# Main_Board1.net
KiCad netlist of a schematic drawn in Altium Designer
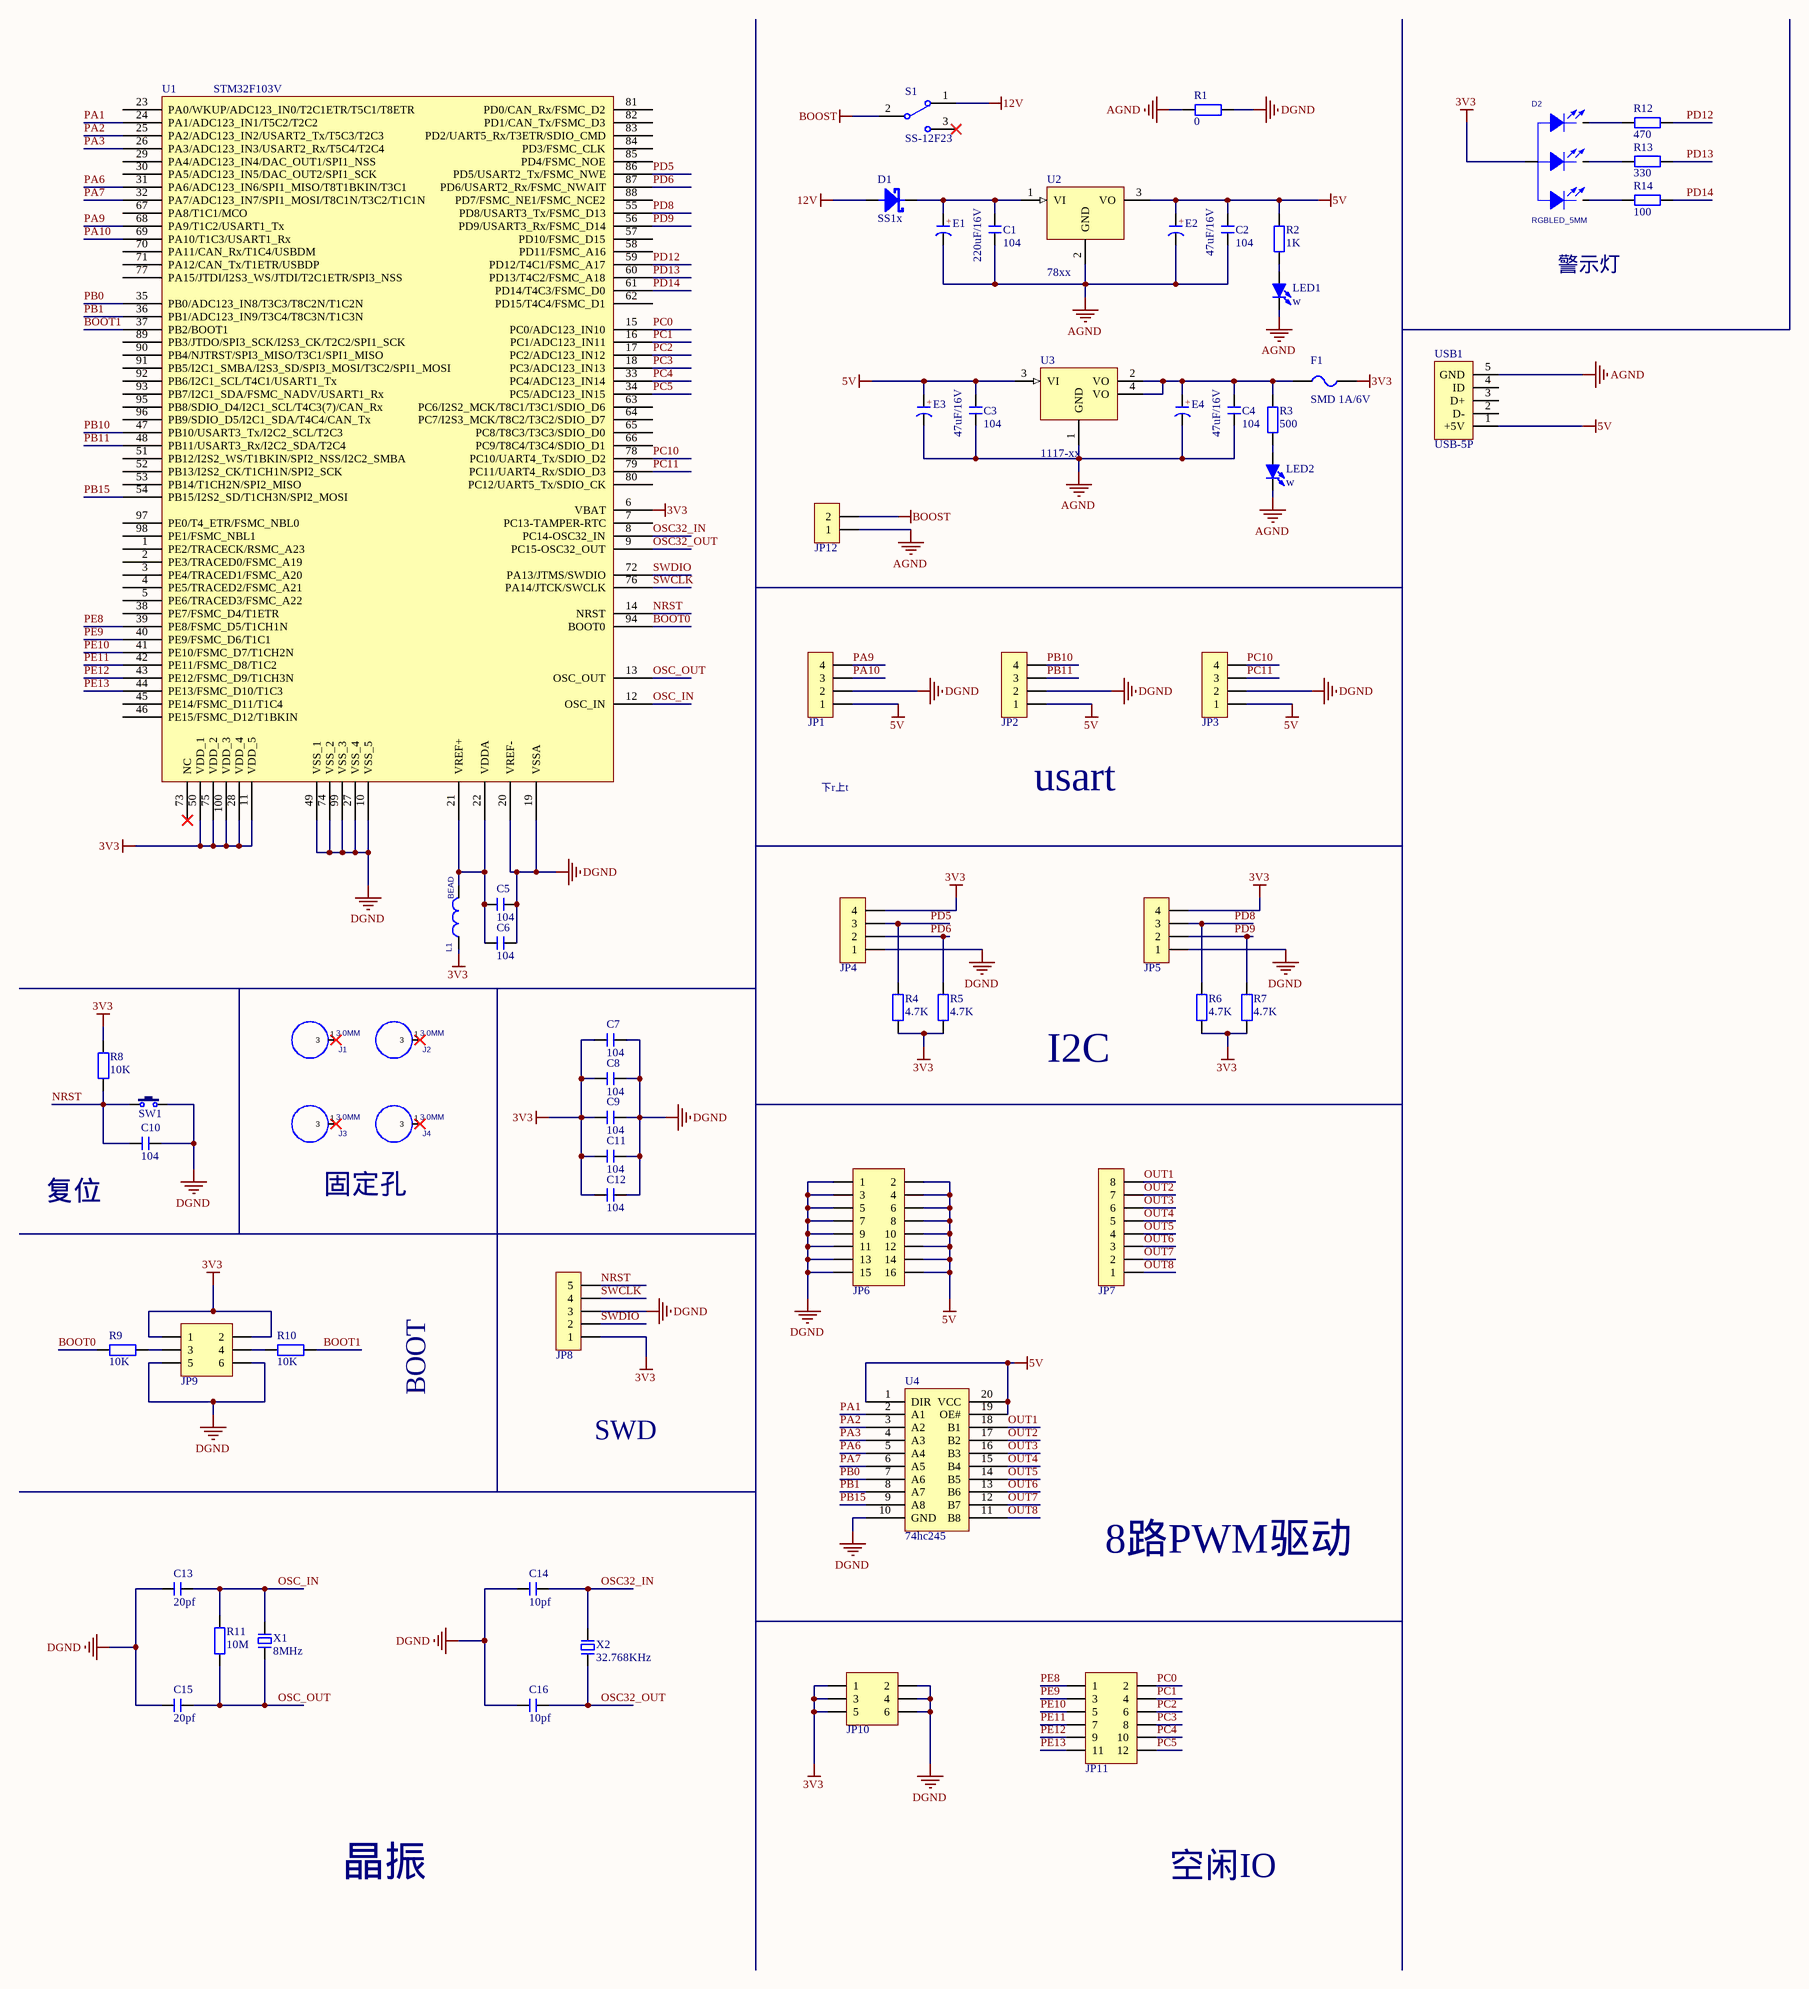
[diagram p0: Main_Board1.SchDoc]

(export (version "E")
  (design (tool "Eeschema 10.0.6"))
  (components
    (comp (ref "C1")
      (value "104")
      (footprint "C 0603")
      (description "无极性贴片电容")
      (fields (field (name "版权归属") "源创客"))
      (libsource (lib "电阻-电容-电感") (part "C"))
    )
    (comp (ref "C2")
      (value "104")
      (footprint "C 0603")
      (description "无极性贴片电容")
      (fields (field (name "版权归属") "源创客"))
      (libsource (lib "电阻-电容-电感") (part "C"))
    )
    (comp (ref "C3")
      (value "104")
      (footprint "C 0603")
      (description "无极性贴片电容")
      (fields (field (name "版权归属") "源创客"))
      (libsource (lib "电阻-电容-电感") (part "C"))
    )
    (comp (ref "C4")
      (value "104")
      (footprint "C 0603")
      (description "无极性贴片电容")
      (fields (field (name "版权归属") "源创客"))
      (libsource (lib "电阻-电容-电感") (part "C"))
    )
    (comp (ref "C5")
      (value "104")
      (footprint "C 0603")
      (description "无极性贴片电容")
      (fields (field (name "版权归属") "源创客"))
      (libsource (lib "电阻-电容-电感") (part "C"))
    )
    (comp (ref "C6")
      (value "104")
      (footprint "C 0603")
      (description "无极性贴片电容")
      (fields (field (name "版权归属") "源创客"))
      (libsource (lib "电阻-电容-电感") (part "C"))
    )
    (comp (ref "C7")
      (value "104")
      (footprint "C 0603")
      (description "无极性贴片电容")
      (fields (field (name "版权归属") "源创客"))
      (libsource (lib "电阻-电容-电感") (part "C"))
    )
    (comp (ref "C8")
      (value "104")
      (footprint "C 0603")
      (description "无极性贴片电容")
      (fields (field (name "版权归属") "源创客"))
      (libsource (lib "电阻-电容-电感") (part "C"))
    )
    (comp (ref "C9")
      (value "104")
      (footprint "C 0603")
      (description "无极性贴片电容")
      (fields (field (name "版权归属") "源创客"))
      (libsource (lib "电阻-电容-电感") (part "C"))
    )
    (comp (ref "C10")
      (value "104")
      (footprint "C 0603")
      (description "无极性贴片电容")
      (fields (field (name "版权归属") "源创客"))
      (libsource (lib "电阻-电容-电感") (part "C"))
    )
    (comp (ref "C11")
      (value "104")
      (footprint "C 0603")
      (description "无极性贴片电容")
      (fields (field (name "版权归属") "源创客"))
      (libsource (lib "电阻-电容-电感") (part "C"))
    )
    (comp (ref "C12")
      (value "104")
      (footprint "C 0603")
      (description "无极性贴片电容")
      (fields (field (name "版权归属") "源创客"))
      (libsource (lib "电阻-电容-电感") (part "C"))
    )
    (comp (ref "C13")
      (value "20pf")
      (footprint "C 0603")
      (description "无极性贴片电容")
      (fields (field (name "版权归属") "源创客"))
      (libsource (lib "电阻-电容-电感") (part "C"))
    )
    (comp (ref "C14")
      (value "10pf")
      (footprint "C 0603")
      (description "无极性贴片电容")
      (fields (field (name "版权归属") "源创客"))
      (libsource (lib "电阻-电容-电感") (part "C"))
    )
    (comp (ref "C15")
      (value "20pf")
      (footprint "C 0603")
      (description "无极性贴片电容")
      (fields (field (name "版权归属") "源创客"))
      (libsource (lib "电阻-电容-电感") (part "C"))
    )
    (comp (ref "C16")
      (value "10pf")
      (footprint "C 0603")
      (description "无极性贴片电容")
      (fields (field (name "版权归属") "源创客"))
      (libsource (lib "电阻-电容-电感") (part "C"))
    )
    (comp (ref "D1")
      (value "SS1x")
      (footprint "SMA")
      (description "Schottky Diode")
      (libsource (lib "General") (part "SS1x"))
    )
    (comp (ref "D2")
      (value "RGBLED_5MM")
      (footprint "LED_RGB_5MM")
      (description "RGB")
      (fields (field (name "Comment") "LED_RGB_5MM"))
      (libsource (lib "MINI-V3") (part "LED_RGB_5MM"))
    )
    (comp (ref "E1")
      (value "220uF/16V")
      (footprint "CD A(3216)")
      (description "贴片钽电容")
      (fields (field (name "版权归属") "源创客"))
      (libsource (lib "电阻-电容-电感") (part "C-CD"))
    )
    (comp (ref "E2")
      (value "47uF/16V")
      (footprint "CD A(3216)")
      (description "贴片钽电容")
      (fields (field (name "版权归属") "源创客"))
      (libsource (lib "电阻-电容-电感") (part "C-CD"))
    )
    (comp (ref "E3")
      (value "47uF/16V")
      (footprint "CD A(3216)")
      (description "贴片钽电容")
      (fields (field (name "版权归属") "源创客"))
      (libsource (lib "电阻-电容-电感") (part "C-CD"))
    )
    (comp (ref "E4")
      (value "47uF/16V")
      (footprint "CD A(3216)")
      (description "贴片钽电容")
      (fields (field (name "版权归属") "源创客"))
      (libsource (lib "电阻-电容-电感") (part "C-CD"))
    )
    (comp (ref "F1")
      (value "SMD 1A/6V")
      (footprint "FU 0805")
      (description "贴片保险丝")
      (fields (field (name "版权归属") "源创客"))
      (libsource (lib "保险丝-晶振") (part "FU"))
    )
    (comp (ref "J1") (value "3.0MM") (footprint "3.0MM-5") (libsource (lib "MINI-V3") (part "3.0MM")))
    (comp (ref "J2") (value "3.0MM") (footprint "3.0MM-5") (libsource (lib "MINI-V3") (part "3.0MM")))
    (comp (ref "J3") (value "3.0MM") (footprint "3.0MM-5") (libsource (lib "MINI-V3") (part "3.0MM")))
    (comp (ref "J4") (value "3.0MM") (footprint "3.0MM-5") (libsource (lib "MINI-V3") (part "3.0MM")))
    (comp (ref "JP1")
      (value "HDR-1X4")
      (footprint "HDR-1X4")
      (description "4P接插件")
      (fields (field (name "版权归属") "源创客"))
      (libsource (lib "接插件") (part "Header 4"))
    )
    (comp (ref "JP2")
      (value "HDR-1X4")
      (footprint "HDR-1X4")
      (description "4P接插件")
      (fields (field (name "版权归属") "源创客"))
      (libsource (lib "接插件") (part "Header 4"))
    )
    (comp (ref "JP3")
      (value "HDR-1X4")
      (footprint "HDR-1X4")
      (description "4P接插件")
      (fields (field (name "版权归属") "源创客"))
      (libsource (lib "接插件") (part "Header 4"))
    )
    (comp (ref "JP4")
      (value "HDR-1X4")
      (footprint "HDR-1X4")
      (description "4P接插件")
      (fields (field (name "版权归属") "源创客"))
      (libsource (lib "接插件") (part "Header 4"))
    )
    (comp (ref "JP5")
      (value "HDR-1X4")
      (footprint "HDR-1X4")
      (description "4P接插件")
      (fields (field (name "版权归属") "源创客"))
      (libsource (lib "接插件") (part "Header 4"))
    )
    (comp (ref "JP6")
      (value "Header 8X2")
      (footprint "HDR-8X2")
      (description "8*2P接插件")
      (fields (field (name "版权归属") "源创客"))
      (libsource (lib "接插件") (part "Header 8X2"))
    )
    (comp (ref "JP7")
      (value "HDR-1X8")
      (footprint "HDR-1X8")
      (description "8P接插件")
      (fields (field (name "版权归属") "源创客"))
      (libsource (lib "接插件") (part "Header 8"))
    )
    (comp (ref "JP8")
      (value "HDR-1X5")
      (footprint "XH2.54-5P")
      (description "5P接插件")
      (fields (field (name "版权归属") "源创客"))
      (libsource (lib "接插件") (part "Header 5"))
    )
    (comp (ref "JP9")
      (value "Header3X2")
      (footprint "HDR-3X2")
      (description "3*2P接插件")
      (fields (field (name "版权归属") "源创客"))
      (libsource (lib "接插件") (part "Header 3X2"))
    )
    (comp (ref "JP10")
      (value "Header3X2")
      (footprint "HDR-3X2")
      (description "3*2P接插件")
      (fields (field (name "版权归属") "源创客"))
      (libsource (lib "接插件") (part "Header 3X2"))
    )
    (comp (ref "JP11")
      (value "Header 6X2")
      (footprint "HDR-6X2")
      (description "6*2P接插件")
      (fields (field (name "版权归属") "源创客"))
      (libsource (lib "接插件") (part "Header  6X2"))
    )
    (comp (ref "JP12")
      (value "HDR-1X2")
      (footprint "KF128-5.08-2P")
      (description "2P接插件")
      (fields (field (name "版权归属") "源创客"))
      (libsource (lib "接插件") (part "Header 2"))
    )
    (comp (ref "L1")
      (value "BEAD")
      (footprint "L0603")
      (description "0603,BEAD")
      (fields (field (name "Comment") "BEAD-220/100MHZ-0603"))
      (libsource (lib "MINI-V3") (part "BEAD-220/100MHZ-0603"))
    )
    (comp (ref "LED1")
      (value "w")
      (footprint "LED 0603W")
      (description "贴片LED")
      (fields (field (name "版权归属") "源创客"))
      (libsource (lib "LED") (part "LED-SMD"))
    )
    (comp (ref "LED2")
      (value "w")
      (footprint "LED 0603W")
      (description "贴片LED")
      (fields (field (name "版权归属") "源创客"))
      (libsource (lib "LED") (part "LED-SMD"))
    )
    (comp (ref "R1")
      (value "0")
      (footprint "R 0603")
      (description "贴片电阻")
      (fields (field (name "版权归属") "源创客"))
      (libsource (lib "电阻-电容-电感") (part "R"))
    )
    (comp (ref "R2")
      (value "1K")
      (footprint "R 0603")
      (description "贴片电阻")
      (fields (field (name "版权归属") "源创客"))
      (libsource (lib "电阻-电容-电感") (part "R"))
    )
    (comp (ref "R3")
      (value "500")
      (footprint "R 0603")
      (description "贴片电阻")
      (fields (field (name "版权归属") "源创客"))
      (libsource (lib "电阻-电容-电感") (part "R"))
    )
    (comp (ref "R4")
      (value "4.7K")
      (footprint "R 0603")
      (description "贴片电阻")
      (fields (field (name "版权归属") "源创客"))
      (libsource (lib "电阻-电容-电感") (part "R"))
    )
    (comp (ref "R5")
      (value "4.7K")
      (footprint "R 0603")
      (description "贴片电阻")
      (fields (field (name "版权归属") "源创客"))
      (libsource (lib "电阻-电容-电感") (part "R"))
    )
    (comp (ref "R6")
      (value "4.7K")
      (footprint "R 0603")
      (description "贴片电阻")
      (fields (field (name "版权归属") "源创客"))
      (libsource (lib "电阻-电容-电感") (part "R"))
    )
    (comp (ref "R7")
      (value "4.7K")
      (footprint "R 0603")
      (description "贴片电阻")
      (fields (field (name "版权归属") "源创客"))
      (libsource (lib "电阻-电容-电感") (part "R"))
    )
    (comp (ref "R8")
      (value "10K")
      (footprint "R 0603")
      (description "贴片电阻")
      (fields (field (name "版权归属") "源创客"))
      (libsource (lib "电阻-电容-电感") (part "R"))
    )
    (comp (ref "R9")
      (value "10K")
      (footprint "R 0603")
      (description "贴片电阻")
      (fields (field (name "版权归属") "源创客"))
      (libsource (lib "电阻-电容-电感") (part "R"))
    )
    (comp (ref "R10")
      (value "10K")
      (footprint "R 0603")
      (description "贴片电阻")
      (fields (field (name "版权归属") "源创客"))
      (libsource (lib "电阻-电容-电感") (part "R"))
    )
    (comp (ref "R11")
      (value "10M")
      (footprint "R 0603")
      (description "贴片电阻")
      (fields (field (name "版权归属") "源创客"))
      (libsource (lib "电阻-电容-电感") (part "R"))
    )
    (comp (ref "R12")
      (value "470")
      (footprint "R 0603")
      (description "贴片电阻")
      (fields (field (name "版权归属") "源创客"))
      (libsource (lib "电阻-电容-电感") (part "R"))
    )
    (comp (ref "R13")
      (value "330")
      (footprint "R 0603")
      (description "贴片电阻")
      (fields (field (name "版权归属") "源创客"))
      (libsource (lib "电阻-电容-电感") (part "R"))
    )
    (comp (ref "R14")
      (value "100")
      (footprint "R 0603")
      (description "贴片电阻")
      (fields (field (name "版权归属") "源创客"))
      (libsource (lib "电阻-电容-电感") (part "R"))
    )
    (comp (ref "S1")
      (value "SS-12F23")
      (footprint "SS-12D10")
      (description "1路波动开关")
      (fields (field (name "版权归属") "源创客"))
      (libsource (lib "按键-开关") (part "SSW-1P"))
    )
    (comp (ref "SW1")
      (value "3x6x5")
      (footprint "TSW SMD-3*6*2.5")
      (description "3x6轻触开关")
      (fields (field (name "版权归属") "源创客"))
      (libsource (lib "按键-开关") (part "TSW 3x6"))
    )
    (comp (ref "U1")
      (value "STM32F103V")
      (footprint "LQFP100 14X14_N")
      (description "32位STM单片机100引脚")
      (fields (field (name "版权归属") "源创客"))
      (libsource (lib "STM32系列单片机") (part "STM32F103V"))
    )
    (comp (ref "U2")
      (value "78xx")
      (footprint "TO252")
      (description "Linear Regulator")
      (libsource (lib "General") (part "78xx"))
    )
    (comp (ref "U3")
      (value "1117-xx")
      (footprint "SOT223_M")
      (description "Linear Regulator")
      (libsource (lib "General") (part "1117"))
    )
    (comp (ref "U4")
      (value "74hc245")
      (footprint "SOP20_L")
      (description "总线收发器")
      (libsource (lib "74系列芯片") (part "74hc245"))
    )
    (comp (ref "USB1")
      (value "USB-5P")
      (footprint "USB-MICRO_A")
      (description "微型USB母座")
      (fields (field (name "版权归属") "源创客"))
      (libsource (lib "接口类") (part "USB-5P"))
    )
    (comp (ref "X1")
      (value "8MHz")
      (footprint "XTAL-49S SMD")
      (description "2脚晶振")
      (fields (field (name "版权归属") "源创客"))
      (libsource (lib "保险丝-晶振") (part "XTAL-2"))
    )
    (comp (ref "X2")
      (value "32.768KHz")
      (footprint "XTAL-3215")
      (description "2脚晶振")
      (fields (field (name "版权归属") "源创客"))
      (libsource (lib "保险丝-晶振") (part "XTAL-2"))
    )
  )
  (nets
    (net (code "1") (name "/BOOT0") (class "Default")
      (node (ref "R9") (pin "2") (pinfunction "2_2") (pintype "passive"))
      (node (ref "U1") (pin "94") (pinfunction "BOOT0_94") (pintype "passive"))
    )
    (net (code "2") (name "/BOOT1") (class "Default")
      (node (ref "R10") (pin "1") (pinfunction "1_1") (pintype "passive"))
      (node (ref "U1") (pin "37") (pinfunction "PB2/BOOT1_37") (pintype "passive"))
    )
    (net (code "3") (name "/NRST") (class "Default")
      (node (ref "C10") (pin "1") (pinfunction "1_1") (pintype "passive"))
      (node (ref "JP8") (pin "5") (pinfunction "5_5") (pintype "passive"))
      (node (ref "R8") (pin "1") (pinfunction "1_1") (pintype "passive"))
      (node (ref "SW1") (pin "1") (pinfunction "1_1") (pintype "passive"))
      (node (ref "U1") (pin "14") (pinfunction "NRST_14") (pintype "passive"))
    )
    (net (code "4") (name "/OSC32_IN") (class "Default")
      (node (ref "C14") (pin "2") (pinfunction "2_2") (pintype "passive"))
      (node (ref "U1") (pin "8") (pinfunction "PC14-OSC32_IN_8") (pintype "passive"))
      (node (ref "X2") (pin "2") (pinfunction "2_2") (pintype "passive"))
    )
    (net (code "5") (name "/OSC32_OUT") (class "Default")
      (node (ref "C16") (pin "2") (pinfunction "2_2") (pintype "passive"))
      (node (ref "U1") (pin "9") (pinfunction "PC15-OSC32_OUT_9") (pintype "passive"))
      (node (ref "X2") (pin "1") (pinfunction "1_1") (pintype "passive"))
    )
    (net (code "6") (name "/OSC_IN") (class "Default")
      (node (ref "C13") (pin "2") (pinfunction "2_2") (pintype "passive"))
      (node (ref "R11") (pin "1") (pinfunction "1_1") (pintype "passive"))
      (node (ref "U1") (pin "12") (pinfunction "OSC_IN_12") (pintype "passive"))
      (node (ref "X1") (pin "2") (pinfunction "2_2") (pintype "passive"))
    )
    (net (code "7") (name "/OSC_OUT") (class "Default")
      (node (ref "C15") (pin "2") (pinfunction "2_2") (pintype "passive"))
      (node (ref "R11") (pin "2") (pinfunction "2_2") (pintype "passive"))
      (node (ref "U1") (pin "13") (pinfunction "OSC_OUT_13") (pintype "passive"))
      (node (ref "X1") (pin "1") (pinfunction "1_1") (pintype "passive"))
    )
    (net (code "8") (name "/OUT1") (class "Default")
      (node (ref "JP7") (pin "8") (pinfunction "8_8") (pintype "passive"))
      (node (ref "U4") (pin "18") (pinfunction "B1_18") (pintype "passive"))
    )
    (net (code "9") (name "/OUT2") (class "Default")
      (node (ref "JP7") (pin "7") (pinfunction "7_7") (pintype "passive"))
      (node (ref "U4") (pin "17") (pinfunction "B2_17") (pintype "passive"))
    )
    (net (code "10") (name "/OUT3") (class "Default")
      (node (ref "JP7") (pin "6") (pinfunction "6_6") (pintype "passive"))
      (node (ref "U4") (pin "16") (pinfunction "B3_16") (pintype "passive"))
    )
    (net (code "11") (name "/OUT4") (class "Default")
      (node (ref "JP7") (pin "5") (pinfunction "5_5") (pintype "passive"))
      (node (ref "U4") (pin "15") (pinfunction "B4_15") (pintype "passive"))
    )
    (net (code "12") (name "/OUT5") (class "Default")
      (node (ref "JP7") (pin "4") (pinfunction "4_4") (pintype "passive"))
      (node (ref "U4") (pin "14") (pinfunction "B5_14") (pintype "passive"))
    )
    (net (code "13") (name "/OUT6") (class "Default")
      (node (ref "JP7") (pin "3") (pinfunction "3_3") (pintype "passive"))
      (node (ref "U4") (pin "13") (pinfunction "B6_13") (pintype "passive"))
    )
    (net (code "14") (name "/OUT7") (class "Default")
      (node (ref "JP7") (pin "2") (pinfunction "2_2") (pintype "passive"))
      (node (ref "U4") (pin "12") (pinfunction "B7_12") (pintype "passive"))
    )
    (net (code "15") (name "/OUT8") (class "Default")
      (node (ref "JP7") (pin "1") (pinfunction "1_1") (pintype "passive"))
      (node (ref "U4") (pin "11") (pinfunction "B8_11") (pintype "passive"))
    )
    (net (code "16") (name "/PA1") (class "Default")
      (node (ref "U1") (pin "24") (pinfunction "PA1/ADC123_IN1/T5C2/T2C2_24") (pintype "passive"))
      (node (ref "U4") (pin "2") (pinfunction "A1_2") (pintype "passive"))
    )
    (net (code "17") (name "/PA2") (class "Default")
      (node (ref "U1") (pin "25") (pinfunction "PA2/ADC123_IN2/USART2_Tx/T5C3/T2C3_25") (pintype "passive"))
      (node (ref "U4") (pin "3") (pinfunction "A2_3") (pintype "passive"))
    )
    (net (code "18") (name "/PA3") (class "Default")
      (node (ref "U1") (pin "26") (pinfunction "PA3/ADC123_IN3/USART2_Rx/T5C4/T2C4_26") (pintype "passive"))
      (node (ref "U4") (pin "4") (pinfunction "A3_4") (pintype "passive"))
    )
    (net (code "19") (name "/PA6") (class "Default")
      (node (ref "U1") (pin "31") (pinfunction "PA6/ADC123_IN6/SPI1_MISO/T8T1BKIN/T3C1_31") (pintype "passive"))
      (node (ref "U4") (pin "5") (pinfunction "A4_5") (pintype "passive"))
    )
    (net (code "20") (name "/PA7") (class "Default")
      (node (ref "U1") (pin "32") (pinfunction "PA7/ADC123_IN7/SPI1_MOSI/T8C1N/T3C2/T1C1N_32") (pintype "passive"))
      (node (ref "U4") (pin "6") (pinfunction "A5_6") (pintype "passive"))
    )
    (net (code "21") (name "/PA9") (class "Default")
      (node (ref "JP1") (pin "4") (pinfunction "4_4") (pintype "passive"))
      (node (ref "U1") (pin "68") (pinfunction "PA9/T1C2/USART1_Tx_68") (pintype "passive"))
    )
    (net (code "22") (name "/PA10") (class "Default")
      (node (ref "JP1") (pin "3") (pinfunction "3_3") (pintype "passive"))
      (node (ref "U1") (pin "69") (pinfunction "PA10/T1C3/USART1_Rx_69") (pintype "passive"))
    )
    (net (code "23") (name "/PB0") (class "Default")
      (node (ref "U1") (pin "35") (pinfunction "PB0/ADC123_IN8/T3C3/T8C2N/T1C2N_35") (pintype "passive"))
      (node (ref "U4") (pin "7") (pinfunction "A6_7") (pintype "passive"))
    )
    (net (code "24") (name "/PB1") (class "Default")
      (node (ref "U1") (pin "36") (pinfunction "PB1/ADC123_IN9/T3C4/T8C3N/T1C3N_36") (pintype "passive"))
      (node (ref "U4") (pin "8") (pinfunction "A7_8") (pintype "passive"))
    )
    (net (code "25") (name "/PB10") (class "Default")
      (node (ref "JP2") (pin "4") (pinfunction "4_4") (pintype "passive"))
      (node (ref "U1") (pin "47") (pinfunction "PB10/USART3_Tx/I2C2_SCL/T2C3_47") (pintype "passive"))
    )
    (net (code "26") (name "/PB11") (class "Default")
      (node (ref "JP2") (pin "3") (pinfunction "3_3") (pintype "passive"))
      (node (ref "U1") (pin "48") (pinfunction "PB11/USART3_Rx/I2C2_SDA/T2C4_48") (pintype "passive"))
    )
    (net (code "27") (name "/PB15") (class "Default")
      (node (ref "U1") (pin "54") (pinfunction "PB15/I2S2_SD/T1CH3N/SPI2_MOSI_54") (pintype "passive"))
      (node (ref "U4") (pin "9") (pinfunction "A8_9") (pintype "passive"))
    )
    (net (code "28") (name "/PC0") (class "Default")
      (node (ref "JP11") (pin "2") (pinfunction "2_2") (pintype "passive"))
      (node (ref "U1") (pin "15") (pinfunction "PC0/ADC123_IN10_15") (pintype "passive"))
    )
    (net (code "29") (name "/PC1") (class "Default")
      (node (ref "JP11") (pin "4") (pinfunction "4_4") (pintype "passive"))
      (node (ref "U1") (pin "16") (pinfunction "PC1/ADC123_IN11_16") (pintype "passive"))
    )
    (net (code "30") (name "/PC2") (class "Default")
      (node (ref "JP11") (pin "6") (pinfunction "6_6") (pintype "passive"))
      (node (ref "U1") (pin "17") (pinfunction "PC2/ADC123_IN12_17") (pintype "passive"))
    )
    (net (code "31") (name "/PC3") (class "Default")
      (node (ref "JP11") (pin "8") (pinfunction "8_8") (pintype "passive"))
      (node (ref "U1") (pin "18") (pinfunction "PC3/ADC123_IN13_18") (pintype "passive"))
    )
    (net (code "32") (name "/PC4") (class "Default")
      (node (ref "JP11") (pin "10") (pinfunction "10_10") (pintype "passive"))
      (node (ref "U1") (pin "33") (pinfunction "PC4/ADC123_IN14_33") (pintype "passive"))
    )
    (net (code "33") (name "/PC5") (class "Default")
      (node (ref "JP11") (pin "12") (pinfunction "12_12") (pintype "passive"))
      (node (ref "U1") (pin "34") (pinfunction "PC5/ADC123_IN15_34") (pintype "passive"))
    )
    (net (code "34") (name "/PC10") (class "Default")
      (node (ref "JP3") (pin "4") (pinfunction "4_4") (pintype "passive"))
      (node (ref "U1") (pin "78") (pinfunction "PC10/UART4_Tx/SDIO_D2_78") (pintype "passive"))
    )
    (net (code "35") (name "/PC11") (class "Default")
      (node (ref "JP3") (pin "3") (pinfunction "3_3") (pintype "passive"))
      (node (ref "U1") (pin "79") (pinfunction "PC11/UART4_Rx/SDIO_D3_79") (pintype "passive"))
    )
    (net (code "36") (name "/PD5") (class "Default")
      (node (ref "JP4") (pin "3") (pinfunction "3_3") (pintype "passive"))
      (node (ref "R4") (pin "2") (pinfunction "2_2") (pintype "passive"))
      (node (ref "U1") (pin "86") (pinfunction "PD5/USART2_Tx/FSMC_NWE_86") (pintype "passive"))
    )
    (net (code "37") (name "/PD6") (class "Default")
      (node (ref "JP4") (pin "2") (pinfunction "2_2") (pintype "passive"))
      (node (ref "R5") (pin "2") (pinfunction "2_2") (pintype "passive"))
      (node (ref "U1") (pin "87") (pinfunction "PD6/USART2_Rx/FSMC_NWAIT_87") (pintype "passive"))
    )
    (net (code "38") (name "/PD8") (class "Default")
      (node (ref "JP5") (pin "3") (pinfunction "3_3") (pintype "passive"))
      (node (ref "R6") (pin "2") (pinfunction "2_2") (pintype "passive"))
      (node (ref "U1") (pin "55") (pinfunction "PD8/USART3_Tx/FSMC_D13_55") (pintype "passive"))
    )
    (net (code "39") (name "/PD9") (class "Default")
      (node (ref "JP5") (pin "2") (pinfunction "2_2") (pintype "passive"))
      (node (ref "R7") (pin "2") (pinfunction "2_2") (pintype "passive"))
      (node (ref "U1") (pin "56") (pinfunction "PD9/USART3_Rx/FSMC_D14_56") (pintype "passive"))
    )
    (net (code "40") (name "/PD12") (class "Default")
      (node (ref "R12") (pin "2") (pinfunction "2_2") (pintype "passive"))
      (node (ref "U1") (pin "59") (pinfunction "PD12/T4C1/FSMC_A17_59") (pintype "passive"))
    )
    (net (code "41") (name "/PD13") (class "Default")
      (node (ref "R13") (pin "2") (pinfunction "2_2") (pintype "passive"))
      (node (ref "U1") (pin "60") (pinfunction "PD13/T4C2/FSMC_A18_60") (pintype "passive"))
    )
    (net (code "42") (name "/PD14") (class "Default")
      (node (ref "R14") (pin "2") (pinfunction "2_2") (pintype "passive"))
      (node (ref "U1") (pin "61") (pinfunction "PD14/T4C3/FSMC_D0_61") (pintype "passive"))
    )
    (net (code "43") (name "/PE8") (class "Default")
      (node (ref "JP11") (pin "1") (pinfunction "1_1") (pintype "passive"))
      (node (ref "U1") (pin "39") (pinfunction "PE8/FSMC_D5/T1CH1N_39") (pintype "passive"))
    )
    (net (code "44") (name "/PE9") (class "Default")
      (node (ref "JP11") (pin "3") (pinfunction "3_3") (pintype "passive"))
      (node (ref "U1") (pin "40") (pinfunction "PE9/FSMC_D6/T1C1_40") (pintype "passive"))
    )
    (net (code "45") (name "/PE10") (class "Default")
      (node (ref "JP11") (pin "5") (pinfunction "5_5") (pintype "passive"))
      (node (ref "U1") (pin "41") (pinfunction "PE10/FSMC_D7/T1CH2N_41") (pintype "passive"))
    )
    (net (code "46") (name "/PE11") (class "Default")
      (node (ref "JP11") (pin "7") (pinfunction "7_7") (pintype "passive"))
      (node (ref "U1") (pin "42") (pinfunction "PE11/FSMC_D8/T1C2_42") (pintype "passive"))
    )
    (net (code "47") (name "/PE12") (class "Default")
      (node (ref "JP11") (pin "9") (pinfunction "9_9") (pintype "passive"))
      (node (ref "U1") (pin "43") (pinfunction "PE12/FSMC_D9/T1CH3N_43") (pintype "passive"))
    )
    (net (code "48") (name "/PE13") (class "Default")
      (node (ref "JP11") (pin "11") (pinfunction "11_11") (pintype "passive"))
      (node (ref "U1") (pin "44") (pinfunction "PE13/FSMC_D10/T1C3_44") (pintype "passive"))
    )
    (net (code "49") (name "/SWCLK") (class "Default")
      (node (ref "JP8") (pin "4") (pinfunction "4_4") (pintype "passive"))
      (node (ref "U1") (pin "76") (pinfunction "PA14/JTCK/SWCLK_76") (pintype "passive"))
    )
    (net (code "50") (name "/SWDIO") (class "Default")
      (node (ref "JP8") (pin "2") (pinfunction "2_2") (pintype "passive"))
      (node (ref "U1") (pin "72") (pinfunction "PA13/JTMS/SWDIO_72") (pintype "passive"))
    )
    (net (code "51") (name "3V3") (class "Default")
      (node (ref "C11") (pin "1") (pinfunction "1_1") (pintype "passive"))
      (node (ref "C12") (pin "1") (pinfunction "1_1") (pintype "passive"))
      (node (ref "C7") (pin "1") (pinfunction "1_1") (pintype "passive"))
      (node (ref "C8") (pin "1") (pinfunction "1_1") (pintype "passive"))
      (node (ref "C9") (pin "1") (pinfunction "1_1") (pintype "passive"))
      (node (ref "D2") (pin "1") (pinfunction "G_1") (pintype "passive"))
      (node (ref "F1") (pin "2") (pinfunction "2_2") (pintype "passive"))
      (node (ref "JP10") (pin "1") (pinfunction "1_1") (pintype "passive"))
      (node (ref "JP10") (pin "3") (pinfunction "3_3") (pintype "passive"))
      (node (ref "JP10") (pin "5") (pinfunction "5_5") (pintype "passive"))
      (node (ref "JP4") (pin "4") (pinfunction "4_4") (pintype "passive"))
      (node (ref "JP5") (pin "4") (pinfunction "4_4") (pintype "passive"))
      (node (ref "JP8") (pin "1") (pinfunction "1_1") (pintype "passive"))
      (node (ref "JP9") (pin "1") (pinfunction "1_1") (pintype "passive"))
      (node (ref "JP9") (pin "2") (pinfunction "2_2") (pintype "passive"))
      (node (ref "L1") (pin "1") (pinfunction "1_1") (pintype "passive"))
      (node (ref "R4") (pin "1") (pinfunction "1_1") (pintype "passive"))
      (node (ref "R5") (pin "1") (pinfunction "1_1") (pintype "passive"))
      (node (ref "R6") (pin "1") (pinfunction "1_1") (pintype "passive"))
      (node (ref "R7") (pin "1") (pinfunction "1_1") (pintype "passive"))
      (node (ref "R8") (pin "2") (pinfunction "2_2") (pintype "passive"))
      (node (ref "U1") (pin "100") (pinfunction "VDD_3_100") (pintype "passive"))
      (node (ref "U1") (pin "11") (pinfunction "VDD_5_11") (pintype "passive"))
      (node (ref "U1") (pin "28") (pinfunction "VDD_4_28") (pintype "passive"))
      (node (ref "U1") (pin "50") (pinfunction "VDD_1_50") (pintype "passive"))
      (node (ref "U1") (pin "6") (pinfunction "VBAT_6") (pintype "passive"))
      (node (ref "U1") (pin "75") (pinfunction "VDD_2_75") (pintype "passive"))
    )
    (net (code "52") (name "5V") (class "Default")
      (node (ref "C2") (pin "2") (pinfunction "2_2") (pintype "passive"))
      (node (ref "C3") (pin "2") (pinfunction "2_2") (pintype "passive"))
      (node (ref "E2") (pin "1") (pinfunction "A_1") (pintype "passive"))
      (node (ref "E3") (pin "1") (pinfunction "A_1") (pintype "passive"))
      (node (ref "JP1") (pin "1") (pinfunction "1_1") (pintype "passive"))
      (node (ref "JP2") (pin "1") (pinfunction "1_1") (pintype "passive"))
      (node (ref "JP3") (pin "1") (pinfunction "1_1") (pintype "passive"))
      (node (ref "JP6") (pin "10") (pinfunction "10_10") (pintype "passive"))
      (node (ref "JP6") (pin "12") (pinfunction "12_12") (pintype "passive"))
      (node (ref "JP6") (pin "14") (pinfunction "14_14") (pintype "passive"))
      (node (ref "JP6") (pin "16") (pinfunction "16_16") (pintype "passive"))
      (node (ref "JP6") (pin "2") (pinfunction "2_2") (pintype "passive"))
      (node (ref "JP6") (pin "4") (pinfunction "4_4") (pintype "passive"))
      (node (ref "JP6") (pin "6") (pinfunction "6_6") (pintype "passive"))
      (node (ref "JP6") (pin "8") (pinfunction "8_8") (pintype "passive"))
      (node (ref "R2") (pin "2") (pinfunction "2_2") (pintype "passive"))
      (node (ref "U2") (pin "3") (pinfunction "VO_3") (pintype "power_in"))
      (node (ref "U3") (pin "3") (pinfunction "VI_3") (pintype "input"))
      (node (ref "U4") (pin "1") (pinfunction "DIR_1") (pintype "passive"))
      (node (ref "U4") (pin "19") (pinfunction "OE#_19") (pintype "passive"))
      (node (ref "U4") (pin "20") (pinfunction "VCC_20") (pintype "passive"))
      (node (ref "USB1") (pin "1") (pinfunction "+5V_1") (pintype "passive"))
    )
    (net (code "53") (name "12V") (class "Default")
      (node (ref "D1") (pin "1") (pinfunction "A_1") (pintype "passive"))
      (node (ref "S1") (pin "1") (pinfunction "1_1") (pintype "passive"))
    )
    (net (code "54") (name "AGND") (class "Default")
      (node (ref "C1") (pin "1") (pinfunction "1_1") (pintype "passive"))
      (node (ref "C2") (pin "1") (pinfunction "1_1") (pintype "passive"))
      (node (ref "C3") (pin "1") (pinfunction "1_1") (pintype "passive"))
      (node (ref "C4") (pin "1") (pinfunction "1_1") (pintype "passive"))
      (node (ref "E1") (pin "2") (pinfunction "K_2") (pintype "passive"))
      (node (ref "E2") (pin "2") (pinfunction "K_2") (pintype "passive"))
      (node (ref "E3") (pin "2") (pinfunction "K_2") (pintype "passive"))
      (node (ref "E4") (pin "2") (pinfunction "K_2") (pintype "passive"))
      (node (ref "JP12") (pin "1") (pinfunction "1_1") (pintype "passive"))
      (node (ref "LED1") (pin "2") (pinfunction "K_2") (pintype "passive"))
      (node (ref "LED2") (pin "2") (pinfunction "K_2") (pintype "passive"))
      (node (ref "R1") (pin "2") (pinfunction "2_2") (pintype "passive"))
      (node (ref "U2") (pin "2") (pinfunction "GND_2") (pintype "power_in"))
      (node (ref "U3") (pin "1") (pinfunction "GND_1") (pintype "power_in"))
      (node (ref "USB1") (pin "5") (pinfunction "GND_5") (pintype "passive"))
    )
    (net (code "55") (name "BOOST") (class "Default")
      (node (ref "JP12") (pin "2") (pinfunction "2_2") (pintype "passive"))
      (node (ref "S1") (pin "2") (pinfunction "2_2") (pintype "passive"))
    )
    (net (code "56") (name "DGND") (class "Default")
      (node (ref "C10") (pin "2") (pinfunction "2_2") (pintype "passive"))
      (node (ref "C11") (pin "2") (pinfunction "2_2") (pintype "passive"))
      (node (ref "C12") (pin "2") (pinfunction "2_2") (pintype "passive"))
      (node (ref "C13") (pin "1") (pinfunction "1_1") (pintype "passive"))
      (node (ref "C14") (pin "1") (pinfunction "1_1") (pintype "passive"))
      (node (ref "C15") (pin "1") (pinfunction "1_1") (pintype "passive"))
      (node (ref "C16") (pin "1") (pinfunction "1_1") (pintype "passive"))
      (node (ref "C5") (pin "2") (pinfunction "2_2") (pintype "passive"))
      (node (ref "C6") (pin "2") (pinfunction "2_2") (pintype "passive"))
      (node (ref "C7") (pin "2") (pinfunction "2_2") (pintype "passive"))
      (node (ref "C8") (pin "2") (pinfunction "2_2") (pintype "passive"))
      (node (ref "C9") (pin "2") (pinfunction "2_2") (pintype "passive"))
      (node (ref "JP1") (pin "2") (pinfunction "2_2") (pintype "passive"))
      (node (ref "JP10") (pin "2") (pinfunction "2_2") (pintype "passive"))
      (node (ref "JP10") (pin "4") (pinfunction "4_4") (pintype "passive"))
      (node (ref "JP10") (pin "6") (pinfunction "6_6") (pintype "passive"))
      (node (ref "JP2") (pin "2") (pinfunction "2_2") (pintype "passive"))
      (node (ref "JP3") (pin "2") (pinfunction "2_2") (pintype "passive"))
      (node (ref "JP4") (pin "1") (pinfunction "1_1") (pintype "passive"))
      (node (ref "JP5") (pin "1") (pinfunction "1_1") (pintype "passive"))
      (node (ref "JP6") (pin "1") (pinfunction "1_1") (pintype "passive"))
      (node (ref "JP6") (pin "11") (pinfunction "11_11") (pintype "passive"))
      (node (ref "JP6") (pin "13") (pinfunction "13_13") (pintype "passive"))
      (node (ref "JP6") (pin "15") (pinfunction "15_15") (pintype "passive"))
      (node (ref "JP6") (pin "3") (pinfunction "3_3") (pintype "passive"))
      (node (ref "JP6") (pin "5") (pinfunction "5_5") (pintype "passive"))
      (node (ref "JP6") (pin "7") (pinfunction "7_7") (pintype "passive"))
      (node (ref "JP6") (pin "9") (pinfunction "9_9") (pintype "passive"))
      (node (ref "JP8") (pin "3") (pinfunction "3_3") (pintype "passive"))
      (node (ref "JP9") (pin "5") (pinfunction "5_5") (pintype "passive"))
      (node (ref "JP9") (pin "6") (pinfunction "6_6") (pintype "passive"))
      (node (ref "R1") (pin "1") (pinfunction "1_1") (pintype "passive"))
      (node (ref "SW1") (pin "2") (pinfunction "2_2") (pintype "passive"))
      (node (ref "U1") (pin "10") (pinfunction "VSS_5_10") (pintype "passive"))
      (node (ref "U1") (pin "19") (pinfunction "VSSA_19") (pintype "passive"))
      (node (ref "U1") (pin "20") (pinfunction "VREF-_20") (pintype "passive"))
      (node (ref "U1") (pin "27") (pinfunction "VSS_4_27") (pintype "passive"))
      (node (ref "U1") (pin "49") (pinfunction "VSS_1_49") (pintype "passive"))
      (node (ref "U1") (pin "74") (pinfunction "VSS_2_74") (pintype "passive"))
      (node (ref "U1") (pin "99") (pinfunction "VSS_3_99") (pintype "passive"))
      (node (ref "U4") (pin "10") (pinfunction "GND_10") (pintype "passive"))
    )
    (net (code "57") (name "Net-(D1-C)") (class "Default")
      (node (ref "C1") (pin "2") (pinfunction "2_2") (pintype "passive"))
      (node (ref "D1") (pin "2") (pinfunction "C_2") (pintype "passive"))
      (node (ref "E1") (pin "1") (pinfunction "A_1") (pintype "passive"))
      (node (ref "U2") (pin "1") (pinfunction "VI_1") (pintype "input"))
    )
    (net (code "58") (name "Net-(D2-G-Pad2)") (class "Default")
      (node (ref "D2") (pin "2") (pinfunction "G_2") (pintype "passive"))
      (node (ref "R12") (pin "1") (pinfunction "1_1") (pintype "passive"))
    )
    (net (code "59") (name "Net-(D2-R-Pad3)") (class "Default")
      (node (ref "D2") (pin "3") (pinfunction "R_3") (pintype "passive"))
      (node (ref "R13") (pin "1") (pinfunction "1_1") (pintype "passive"))
    )
    (net (code "60") (name "Net-(D2-R-Pad4)") (class "Default")
      (node (ref "D2") (pin "4") (pinfunction "R_4") (pintype "passive"))
      (node (ref "R14") (pin "1") (pinfunction "1_1") (pintype "passive"))
    )
    (net (code "61") (name "Net-(E4-A)") (class "Default")
      (node (ref "C4") (pin "2") (pinfunction "2_2") (pintype "passive"))
      (node (ref "E4") (pin "1") (pinfunction "A_1") (pintype "passive"))
      (node (ref "F1") (pin "1") (pinfunction "1_1") (pintype "passive"))
      (node (ref "R3") (pin "2") (pinfunction "2_2") (pintype "passive"))
      (node (ref "U3") (pin "2") (pinfunction "VO_2") (pintype "power_in"))
      (node (ref "U3") (pin "4") (pinfunction "VO_4") (pintype "power_in"))
    )
    (net (code "62") (name "Net-(JP9-Pad3)") (class "Default")
      (node (ref "JP9") (pin "3") (pinfunction "3_3") (pintype "passive"))
      (node (ref "R9") (pin "1") (pinfunction "1_1") (pintype "passive"))
    )
    (net (code "63") (name "Net-(JP9-Pad4)") (class "Default")
      (node (ref "JP9") (pin "4") (pinfunction "4_4") (pintype "passive"))
      (node (ref "R10") (pin "2") (pinfunction "2_2") (pintype "passive"))
    )
    (net (code "64") (name "Net-(LED1-A)") (class "Default")
      (node (ref "LED1") (pin "1") (pinfunction "A_1") (pintype "passive"))
      (node (ref "R2") (pin "1") (pinfunction "1_1") (pintype "passive"))
    )
    (net (code "65") (name "Net-(LED2-A)") (class "Default")
      (node (ref "LED2") (pin "1") (pinfunction "A_1") (pintype "passive"))
      (node (ref "R3") (pin "1") (pinfunction "1_1") (pintype "passive"))
    )
    (net (code "66") (name "Net-(U1-VDDA)") (class "Default")
      (node (ref "C5") (pin "1") (pinfunction "1_1") (pintype "passive"))
      (node (ref "C6") (pin "1") (pinfunction "1_1") (pintype "passive"))
      (node (ref "L1") (pin "2") (pinfunction "2_2") (pintype "passive"))
      (node (ref "U1") (pin "21") (pinfunction "VREF+_21") (pintype "passive"))
      (node (ref "U1") (pin "22") (pinfunction "VDDA_22") (pintype "passive"))
    )
    (net (code "67") (name "unconnected-(J1-3-Pad1)") (class "Default")
      (node (ref "J1") (pin "1") (pinfunction "3_1") (pintype "passive+no_connect"))
    )
    (net (code "68") (name "unconnected-(J2-3-Pad1)") (class "Default")
      (node (ref "J2") (pin "1") (pinfunction "3_1") (pintype "passive+no_connect"))
    )
    (net (code "69") (name "unconnected-(J3-3-Pad1)") (class "Default")
      (node (ref "J3") (pin "1") (pinfunction "3_1") (pintype "passive+no_connect"))
    )
    (net (code "70") (name "unconnected-(J4-3-Pad1)") (class "Default")
      (node (ref "J4") (pin "1") (pinfunction "3_1") (pintype "passive+no_connect"))
    )
    (net (code "71") (name "unconnected-(S1-Pad3)") (class "Default")
      (node (ref "S1") (pin "3") (pinfunction "3_3") (pintype "passive+no_connect"))
    )
    (net (code "72") (name "unconnected-(U1-NC-Pad73)") (class "Default")
      (node (ref "U1") (pin "73") (pinfunction "NC_73") (pintype "passive+no_connect"))
    )
    (net (code "73") (name "unconnected-(U1-PA0{slash}WKUP{slash}ADC123_IN0{slash}T2C1ETR{slash}T5C1{slash}T8ETR-Pad23)") (class "Default")
      (node (ref "U1") (pin "23") (pinfunction "PA0/WKUP/ADC123_IN0/T2C1ETR/T5C1/T8ETR_23") (pintype "passive"))
    )
    (net (code "74") (name "unconnected-(U1-PA4{slash}ADC123_IN4{slash}DAC_OUT1{slash}SPI1_NSS-Pad29)") (class "Default")
      (node (ref "U1") (pin "29") (pinfunction "PA4/ADC123_IN4/DAC_OUT1/SPI1_NSS_29") (pintype "passive"))
    )
    (net (code "75") (name "unconnected-(U1-PA5{slash}ADC123_IN5{slash}DAC_OUT2{slash}SPI1_SCK-Pad30)") (class "Default")
      (node (ref "U1") (pin "30") (pinfunction "PA5/ADC123_IN5/DAC_OUT2/SPI1_SCK_30") (pintype "passive"))
    )
    (net (code "76") (name "unconnected-(U1-PA8{slash}T1C1{slash}MCO-Pad67)") (class "Default")
      (node (ref "U1") (pin "67") (pinfunction "PA8/T1C1/MCO_67") (pintype "passive"))
    )
    (net (code "77") (name "unconnected-(U1-PA11{slash}CAN_Rx{slash}T1C4{slash}USBDM-Pad70)") (class "Default")
      (node (ref "U1") (pin "70") (pinfunction "PA11/CAN_Rx/T1C4/USBDM_70") (pintype "passive"))
    )
    (net (code "78") (name "unconnected-(U1-PA12{slash}CAN_Tx{slash}T1ETR{slash}USBDP-Pad71)") (class "Default")
      (node (ref "U1") (pin "71") (pinfunction "PA12/CAN_Tx/T1ETR/USBDP_71") (pintype "passive"))
    )
    (net (code "79") (name "unconnected-(U1-PA15{slash}JTDI{slash}I2S3_WS{slash}JTDI{slash}T2C1ETR{slash}SPI3_NSS-Pad77)") (class "Default")
      (node (ref "U1") (pin "77") (pinfunction "PA15/JTDI/I2S3_WS/JTDI/T2C1ETR/SPI3_NSS_77") (pintype "passive"))
    )
    (net (code "80") (name "unconnected-(U1-PB3{slash}JTDO{slash}SPI3_SCK{slash}I2S3_CK{slash}T2C2{slash}SPI1_SCK-Pad89)") (class "Default")
      (node (ref "U1") (pin "89") (pinfunction "PB3/JTDO/SPI3_SCK/I2S3_CK/T2C2/SPI1_SCK_89") (pintype "passive"))
    )
    (net (code "81") (name "unconnected-(U1-PB4{slash}NJTRST{slash}SPI3_MISO{slash}T3C1{slash}SPI1_MISO-Pad90)") (class "Default")
      (node (ref "U1") (pin "90") (pinfunction "PB4/NJTRST/SPI3_MISO/T3C1/SPI1_MISO_90") (pintype "passive"))
    )
    (net (code "82") (name "unconnected-(U1-PB5{slash}I2C1_SMBA{slash}I2S3_SD{slash}SPI3_MOSI{slash}T3C2{slash}SPI1_MOSI-Pad91)") (class "Default")
      (node (ref "U1") (pin "91") (pinfunction "PB5/I2C1_SMBA/I2S3_SD/SPI3_MOSI/T3C2/SPI1_MOSI_91") (pintype "passive"))
    )
    (net (code "83") (name "unconnected-(U1-PB6{slash}I2C1_SCL{slash}T4C1{slash}USART1_Tx-Pad92)") (class "Default")
      (node (ref "U1") (pin "92") (pinfunction "PB6/I2C1_SCL/T4C1/USART1_Tx_92") (pintype "passive"))
    )
    (net (code "84") (name "unconnected-(U1-PB7{slash}I2C1_SDA{slash}FSMC_NADV{slash}USART1_Rx-Pad93)") (class "Default")
      (node (ref "U1") (pin "93") (pinfunction "PB7/I2C1_SDA/FSMC_NADV/USART1_Rx_93") (pintype "passive"))
    )
    (net (code "85") (name "unconnected-(U1-PB8{slash}SDIO_D4{slash}I2C1_SCL{slash}T4C3(7){slash}CAN_Rx-Pad95)") (class "Default")
      (node (ref "U1") (pin "95") (pinfunction "PB8/SDIO_D4/I2C1_SCL/T4C3(7)/CAN_Rx_95") (pintype "passive"))
    )
    (net (code "86") (name "unconnected-(U1-PB9{slash}SDIO_D5{slash}I2C1_SDA{slash}T4C4{slash}CAN_Tx-Pad96)") (class "Default")
      (node (ref "U1") (pin "96") (pinfunction "PB9/SDIO_D5/I2C1_SDA/T4C4/CAN_Tx_96") (pintype "passive"))
    )
    (net (code "87") (name "unconnected-(U1-PB12{slash}I2S2_WS{slash}T1BKIN{slash}SPI2_NSS{slash}I2C2_SMBA-Pad51)") (class "Default")
      (node (ref "U1") (pin "51") (pinfunction "PB12/I2S2_WS/T1BKIN/SPI2_NSS/I2C2_SMBA_51") (pintype "passive"))
    )
    (net (code "88") (name "unconnected-(U1-PB13{slash}I2S2_CK{slash}T1CH1N{slash}SPI2_SCK-Pad52)") (class "Default")
      (node (ref "U1") (pin "52") (pinfunction "PB13/I2S2_CK/T1CH1N/SPI2_SCK_52") (pintype "passive"))
    )
    (net (code "89") (name "unconnected-(U1-PB14{slash}T1CH2N{slash}SPI2_MISO-Pad53)") (class "Default")
      (node (ref "U1") (pin "53") (pinfunction "PB14/T1CH2N/SPI2_MISO_53") (pintype "passive"))
    )
    (net (code "90") (name "unconnected-(U1-PC6{slash}I2S2_MCK{slash}T8C1{slash}T3C1{slash}SDIO_D6-Pad63)") (class "Default")
      (node (ref "U1") (pin "63") (pinfunction "PC6/I2S2_MCK/T8C1/T3C1/SDIO_D6_63") (pintype "passive"))
    )
    (net (code "91") (name "unconnected-(U1-PC7{slash}I2S3_MCK{slash}T8C2{slash}T3C2{slash}SDIO_D7-Pad64)") (class "Default")
      (node (ref "U1") (pin "64") (pinfunction "PC7/I2S3_MCK/T8C2/T3C2/SDIO_D7_64") (pintype "passive"))
    )
    (net (code "92") (name "unconnected-(U1-PC8{slash}T8C3{slash}T3C3{slash}SDIO_D0-Pad65)") (class "Default")
      (node (ref "U1") (pin "65") (pinfunction "PC8/T8C3/T3C3/SDIO_D0_65") (pintype "passive"))
    )
    (net (code "93") (name "unconnected-(U1-PC9{slash}T8C4{slash}T3C4{slash}SDIO_D1-Pad66)") (class "Default")
      (node (ref "U1") (pin "66") (pinfunction "PC9/T8C4/T3C4/SDIO_D1_66") (pintype "passive"))
    )
    (net (code "94") (name "unconnected-(U1-PC12{slash}UART5_Tx{slash}SDIO_CK-Pad80)") (class "Default")
      (node (ref "U1") (pin "80") (pinfunction "PC12/UART5_Tx/SDIO_CK_80") (pintype "passive"))
    )
    (net (code "95") (name "unconnected-(U1-PC13-TAMPER-RTC-Pad7)") (class "Default")
      (node (ref "U1") (pin "7") (pinfunction "PC13-TAMPER-RTC_7") (pintype "passive"))
    )
    (net (code "96") (name "unconnected-(U1-PD0{slash}CAN_Rx{slash}FSMC_D2-Pad81)") (class "Default")
      (node (ref "U1") (pin "81") (pinfunction "PD0/CAN_Rx/FSMC_D2_81") (pintype "passive"))
    )
    (net (code "97") (name "unconnected-(U1-PD1{slash}CAN_Tx{slash}FSMC_D3-Pad82)") (class "Default")
      (node (ref "U1") (pin "82") (pinfunction "PD1/CAN_Tx/FSMC_D3_82") (pintype "passive"))
    )
    (net (code "98") (name "unconnected-(U1-PD2{slash}UART5_Rx{slash}T3ETR{slash}SDIO_CMD-Pad83)") (class "Default")
      (node (ref "U1") (pin "83") (pinfunction "PD2/UART5_Rx/T3ETR/SDIO_CMD_83") (pintype "passive"))
    )
    (net (code "99") (name "unconnected-(U1-PD3{slash}FSMC_CLK-Pad84)") (class "Default")
      (node (ref "U1") (pin "84") (pinfunction "PD3/FSMC_CLK_84") (pintype "passive"))
    )
    (net (code "100") (name "unconnected-(U1-PD4{slash}FSMC_NOE-Pad85)") (class "Default")
      (node (ref "U1") (pin "85") (pinfunction "PD4/FSMC_NOE_85") (pintype "passive"))
    )
    (net (code "101") (name "unconnected-(U1-PD7{slash}FSMC_NE1{slash}FSMC_NCE2-Pad88)") (class "Default")
      (node (ref "U1") (pin "88") (pinfunction "PD7/FSMC_NE1/FSMC_NCE2_88") (pintype "passive"))
    )
    (net (code "102") (name "unconnected-(U1-PD10{slash}FSMC_D15-Pad57)") (class "Default")
      (node (ref "U1") (pin "57") (pinfunction "PD10/FSMC_D15_57") (pintype "passive"))
    )
    (net (code "103") (name "unconnected-(U1-PD11{slash}FSMC_A16-Pad58)") (class "Default")
      (node (ref "U1") (pin "58") (pinfunction "PD11/FSMC_A16_58") (pintype "passive"))
    )
    (net (code "104") (name "unconnected-(U1-PD15{slash}T4C4{slash}FSMC_D1-Pad62)") (class "Default")
      (node (ref "U1") (pin "62") (pinfunction "PD15/T4C4/FSMC_D1_62") (pintype "passive"))
    )
    (net (code "105") (name "unconnected-(U1-PE0{slash}T4_ETR{slash}FSMC_NBL0-Pad97)") (class "Default")
      (node (ref "U1") (pin "97") (pinfunction "PE0/T4_ETR/FSMC_NBL0_97") (pintype "passive"))
    )
    (net (code "106") (name "unconnected-(U1-PE1{slash}FSMC_NBL1-Pad98)") (class "Default")
      (node (ref "U1") (pin "98") (pinfunction "PE1/FSMC_NBL1_98") (pintype "passive"))
    )
    (net (code "107") (name "unconnected-(U1-PE2{slash}TRACECK{slash}RSMC_A23-Pad1)") (class "Default")
      (node (ref "U1") (pin "1") (pinfunction "PE2/TRACECK/RSMC_A23_1") (pintype "passive"))
    )
    (net (code "108") (name "unconnected-(U1-PE3{slash}TRACED0{slash}FSMC_A19-Pad2)") (class "Default")
      (node (ref "U1") (pin "2") (pinfunction "PE3/TRACED0/FSMC_A19_2") (pintype "passive"))
    )
    (net (code "109") (name "unconnected-(U1-PE4{slash}TRACED1{slash}FSMC_A20-Pad3)") (class "Default")
      (node (ref "U1") (pin "3") (pinfunction "PE4/TRACED1/FSMC_A20_3") (pintype "passive"))
    )
    (net (code "110") (name "unconnected-(U1-PE5{slash}TRACED2{slash}FSMC_A21-Pad4)") (class "Default")
      (node (ref "U1") (pin "4") (pinfunction "PE5/TRACED2/FSMC_A21_4") (pintype "passive"))
    )
    (net (code "111") (name "unconnected-(U1-PE6{slash}TRACED3{slash}FSMC_A22-Pad5)") (class "Default")
      (node (ref "U1") (pin "5") (pinfunction "PE6/TRACED3/FSMC_A22_5") (pintype "passive"))
    )
    (net (code "112") (name "unconnected-(U1-PE7{slash}FSMC_D4{slash}T1ETR-Pad38)") (class "Default")
      (node (ref "U1") (pin "38") (pinfunction "PE7/FSMC_D4/T1ETR_38") (pintype "passive"))
    )
    (net (code "113") (name "unconnected-(U1-PE14{slash}FSMC_D11{slash}T1C4-Pad45)") (class "Default")
      (node (ref "U1") (pin "45") (pinfunction "PE14/FSMC_D11/T1C4_45") (pintype "passive"))
    )
    (net (code "114") (name "unconnected-(U1-PE15{slash}FSMC_D12{slash}T1BKIN-Pad46)") (class "Default")
      (node (ref "U1") (pin "46") (pinfunction "PE15/FSMC_D12/T1BKIN_46") (pintype "passive"))
    )
    (net (code "115") (name "unconnected-(USB1-D+-Pad3)") (class "Default")
      (node (ref "USB1") (pin "3") (pinfunction "D+_3") (pintype "passive"))
    )
    (net (code "116") (name "unconnected-(USB1-D--Pad2)") (class "Default")
      (node (ref "USB1") (pin "2") (pinfunction "D-_2") (pintype "passive"))
    )
    (net (code "117") (name "unconnected-(USB1-ID-Pad4)") (class "Default")
      (node (ref "USB1") (pin "4") (pinfunction "ID_4") (pintype "passive"))
    )
  )
)
